# Schaltplan.net
KiCad netlist of a schematic drawn in EAGLE
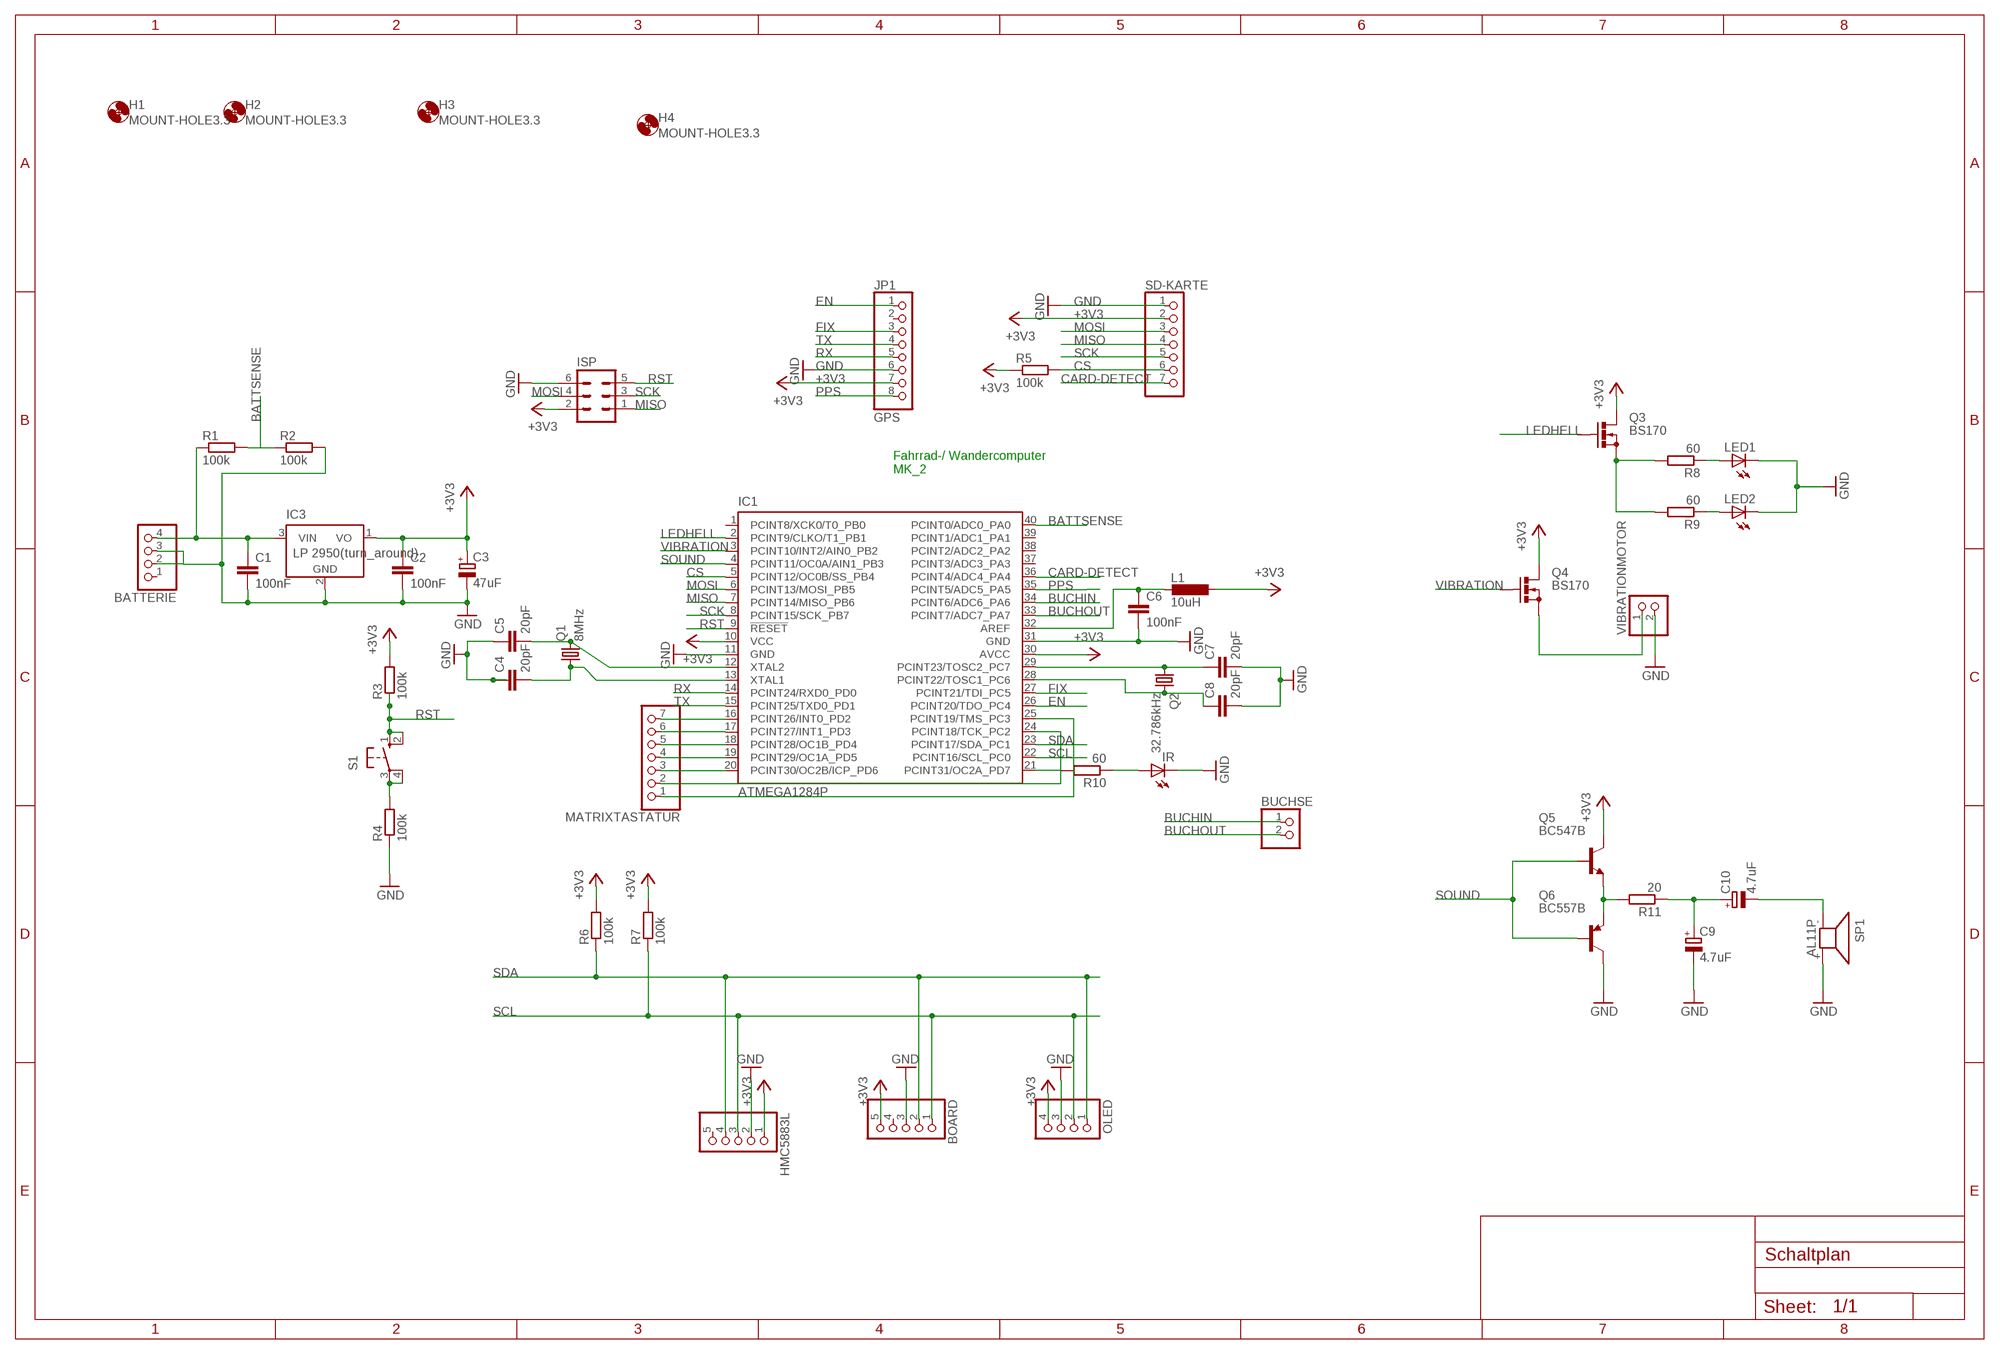
[diagram p0: schematic, sheet 1]

(export (version "E")
  (design (tool "Eeschema 10.0.6"))
  (components
    (comp (ref "BATTERIE")
      (value "PINHD-1X4")
      (footprint "eagle-import:1X04")
      (libsource (lib "eagle-import") (part "PINHD-1X4"))
    )
    (comp (ref "BOARD")
      (value "PINHD-1X5")
      (footprint "eagle-import:1X05")
      (libsource (lib "eagle-import") (part "PINHD-1X5"))
    )
    (comp (ref "BUCHSE")
      (value "PINHD-1X2")
      (footprint "eagle-import:1X02")
      (libsource (lib "eagle-import") (part "PINHD-1X2"))
    )
    (comp (ref "C1")
      (value "100nF")
      (footprint "eagle-import:C025-024X044")
      (libsource (lib "eagle-import") (part "C-EU025-024X044"))
    )
    (comp (ref "C2")
      (value "100nF")
      (footprint "eagle-import:C025-024X044")
      (libsource (lib "eagle-import") (part "C-EU025-024X044"))
    )
    (comp (ref "C3")
      (value "47uF")
      (footprint "eagle-import:E2,5-6")
      (libsource (lib "eagle-import") (part "CPOL-EUE2.5-6"))
    )
    (comp (ref "C4")
      (value "20pF")
      (footprint "eagle-import:C025-024X044")
      (libsource (lib "eagle-import") (part "C-EU025-024X044"))
    )
    (comp (ref "C5")
      (value "20pF")
      (footprint "eagle-import:C025-024X044")
      (libsource (lib "eagle-import") (part "C-EU025-024X044"))
    )
    (comp (ref "C6")
      (value "100nF")
      (footprint "eagle-import:C025-024X044")
      (libsource (lib "eagle-import") (part "C-EU025-024X044"))
    )
    (comp (ref "C7")
      (value "20pF")
      (footprint "eagle-import:C025-024X044")
      (libsource (lib "eagle-import") (part "C-EU025-024X044"))
    )
    (comp (ref "C8")
      (value "20pF")
      (footprint "eagle-import:C025-024X044")
      (libsource (lib "eagle-import") (part "C-EU025-024X044"))
    )
    (comp (ref "C9")
      (value "4.7uF")
      (footprint "eagle-import:E2,5-6")
      (libsource (lib "eagle-import") (part "CPOL-EUE2.5-6"))
    )
    (comp (ref "C10")
      (value "4.7uF")
      (footprint "eagle-import:E2,5-6")
      (libsource (lib "eagle-import") (part "CPOL-EUE2.5-6"))
    )
    (comp (ref "H1")
      (value "MOUNT-HOLE3.3")
      (footprint "eagle-import:3,3")
      (libsource (lib "eagle-import") (part "MOUNT-HOLE3.3"))
    )
    (comp (ref "H2")
      (value "MOUNT-HOLE3.3")
      (footprint "eagle-import:3,3")
      (libsource (lib "eagle-import") (part "MOUNT-HOLE3.3"))
    )
    (comp (ref "H3")
      (value "MOUNT-HOLE3.3")
      (footprint "eagle-import:3,3")
      (libsource (lib "eagle-import") (part "MOUNT-HOLE3.3"))
    )
    (comp (ref "H4")
      (value "MOUNT-HOLE3.3")
      (footprint "eagle-import:3,3")
      (libsource (lib "eagle-import") (part "MOUNT-HOLE3.3"))
    )
    (comp (ref "HMC5883L")
      (value "PINHD-1X5")
      (footprint "eagle-import:1X05")
      (libsource (lib "eagle-import") (part "PINHD-1X5"))
    )
    (comp (ref "IC1")
      (value "ATMEGA1284P")
      (footprint "eagle-import:DIL40")
      (fields (field (name "MPN") "ATMEGA644-20PU"))
      (libsource (lib "eagle-import") (part "ATMEGA644-PU20"))
    )
    (comp (ref "IC3")
      (value "LP 2950(turn_around)")
      (footprint "eagle-import:TO92")
      (fields (field (name "MF") "NATIONAL SEMICONDUCTOR") (field (name "MPN") "LM2936Z-3.0/NOPB"))
      (libsource (lib "eagle-import") (part "LM2936?Z-3.0"))
    )
    (comp (ref "IR")
      (value "LED3MM")
      (footprint "eagle-import:LED3MM")
      (libsource (lib "eagle-import") (part "LED3MM"))
    )
    (comp (ref "ISP")
      (value "ML6")
      (footprint "eagle-import:ML6")
      (libsource (lib "eagle-import") (part "ML6"))
    )
    (comp (ref "JP1")
      (value "GPS")
      (footprint "eagle-import:1X08")
      (libsource (lib "eagle-import") (part "PINHD-1X8"))
    )
    (comp (ref "L1")
      (value "10uH")
      (footprint "eagle-import:0207_10")
      (libsource (lib "eagle-import") (part "L-EU0207/10"))
    )
    (comp (ref "LED1")
      (value "LED5MM")
      (footprint "eagle-import:LED5MM")
      (libsource (lib "eagle-import") (part "LED5MM"))
    )
    (comp (ref "LED2")
      (value "LED5MM")
      (footprint "eagle-import:LED5MM")
      (libsource (lib "eagle-import") (part "LED5MM"))
    )
    (comp (ref "MATRIXTASTATUR")
      (value "PINHD-1X7")
      (footprint "eagle-import:1X07")
      (libsource (lib "eagle-import") (part "PINHD-1X7"))
    )
    (comp (ref "OLED")
      (value "PINHD-1X4")
      (footprint "eagle-import:1X04")
      (libsource (lib "eagle-import") (part "PINHD-1X4"))
    )
    (comp (ref "Q1")
      (value "8MHz")
      (footprint "eagle-import:HC49_S")
      (libsource (lib "eagle-import") (part "CRYSTALHC49S"))
    )
    (comp (ref "Q2")
      (value "32.786kHz")
      (footprint "eagle-import:TC26V")
      (libsource (lib "eagle-import") (part "CRYSTALTC26V"))
    )
    (comp (ref "Q3")
      (value "BS170")
      (footprint "eagle-import:SOT54E")
      (libsource (lib "eagle-import") (part "BS170"))
    )
    (comp (ref "Q4")
      (value "BS170")
      (footprint "eagle-import:SOT54E")
      (libsource (lib "eagle-import") (part "BS170"))
    )
    (comp (ref "Q5")
      (value "BC547B")
      (footprint "eagle-import:TO92")
      (libsource (lib "eagle-import") (part "BC547B"))
    )
    (comp (ref "Q6")
      (value "BC557B")
      (footprint "eagle-import:TO92-EBC")
      (libsource (lib "eagle-import") (part "BC557B"))
    )
    (comp (ref "R1")
      (value "100k")
      (footprint "eagle-import:0207_10")
      (libsource (lib "eagle-import") (part "R-EU_0207/10"))
    )
    (comp (ref "R2")
      (value "100k")
      (footprint "eagle-import:0207_10")
      (libsource (lib "eagle-import") (part "R-EU_0207/10"))
    )
    (comp (ref "R3")
      (value "100k")
      (footprint "eagle-import:0207_10")
      (libsource (lib "eagle-import") (part "R-EU_0207/10"))
    )
    (comp (ref "R4")
      (value "100k")
      (footprint "eagle-import:0207_10")
      (libsource (lib "eagle-import") (part "R-EU_0207/10"))
    )
    (comp (ref "R5")
      (value "100k")
      (footprint "eagle-import:0207_10")
      (libsource (lib "eagle-import") (part "R-EU_0207/10"))
    )
    (comp (ref "R6")
      (value "100k")
      (footprint "eagle-import:0207_10")
      (libsource (lib "eagle-import") (part "R-EU_0207/10"))
    )
    (comp (ref "R7")
      (value "100k")
      (footprint "eagle-import:0207_10")
      (libsource (lib "eagle-import") (part "R-EU_0207/10"))
    )
    (comp (ref "R8")
      (value "60")
      (footprint "eagle-import:0207_10")
      (libsource (lib "eagle-import") (part "R-EU_0207/10"))
    )
    (comp (ref "R9")
      (value "60")
      (footprint "eagle-import:0207_10")
      (libsource (lib "eagle-import") (part "R-EU_0207/10"))
    )
    (comp (ref "R10")
      (value "60")
      (footprint "eagle-import:0207_10")
      (libsource (lib "eagle-import") (part "R-EU_0207/10"))
    )
    (comp (ref "R11")
      (value "20")
      (footprint "eagle-import:0207_10")
      (libsource (lib "eagle-import") (part "R-EU_0207/10"))
    )
    (comp (ref "S1")
      (value "10-XX")
      (footprint "eagle-import:B3F-10XX")
      (fields (field (name "MPN") "B3F-1000"))
      (libsource (lib "eagle-import") (part "10-XX"))
    )
    (comp (ref "SD-KARTE")
      (value "PINHD-1X7")
      (footprint "eagle-import:1X07")
      (libsource (lib "eagle-import") (part "PINHD-1X7"))
    )
    (comp (ref "SP1")
      (value "AL11P")
      (footprint "eagle-import:AL11P")
      (libsource (lib "eagle-import") (part "AL11P"))
    )
    (comp (ref "VIBRATIONMOTOR")
      (value "PINHD-1X2")
      (footprint "eagle-import:1X02")
      (libsource (lib "eagle-import") (part "PINHD-1X2"))
    )
  )
  (nets
    (net (code "1") (name "+3V3") (class "Default")
      (node (ref "BOARD") (pin "5") (pinfunction "5_5") (pintype "passive"))
      (node (ref "C2") (pin "1") (pinfunction "1_1") (pintype "passive"))
      (node (ref "C3") (pin "+") (pinfunction "+_+") (pintype "passive"))
      (node (ref "HMC5883L") (pin "1") (pinfunction "1_1") (pintype "passive"))
      (node (ref "IC1") (pin "10") (pinfunction "VCC_10") (pintype "power_in"))
      (node (ref "IC1") (pin "30") (pinfunction "AVCC_30") (pintype "power_in"))
      (node (ref "IC3") (pin "1") (pinfunction "VO_1") (pintype "passive"))
      (node (ref "ISP") (pin "2") (pinfunction "2_2") (pintype "passive"))
      (node (ref "JP1") (pin "7") (pinfunction "7_7") (pintype "passive"))
      (node (ref "L1") (pin "1") (pinfunction "1_1") (pintype "passive"))
      (node (ref "OLED") (pin "4") (pinfunction "4_4") (pintype "passive"))
      (node (ref "Q3") (pin "D") (pinfunction "D_D") (pintype "passive"))
      (node (ref "Q4") (pin "D") (pinfunction "D_D") (pintype "passive"))
      (node (ref "Q5") (pin "3") (pinfunction "C_3") (pintype "passive"))
      (node (ref "R3") (pin "2") (pinfunction "2_2") (pintype "passive"))
      (node (ref "R5") (pin "1") (pinfunction "1_1") (pintype "passive"))
      (node (ref "R6") (pin "2") (pinfunction "2_2") (pintype "passive"))
      (node (ref "R7") (pin "2") (pinfunction "2_2") (pintype "passive"))
      (node (ref "SD-KARTE") (pin "2") (pinfunction "2_2") (pintype "passive"))
    )
    (net (code "2") (name "/BATTSENSE") (class "Default")
      (node (ref "IC1") (pin "40") (pinfunction "PCINT0/ADC0_PA0_40") (pintype "bidirectional"))
      (node (ref "R1") (pin "2") (pinfunction "2_2") (pintype "passive"))
      (node (ref "R2") (pin "1") (pinfunction "1_1") (pintype "passive"))
    )
    (net (code "3") (name "/BUCHIN") (class "Default")
      (node (ref "BUCHSE") (pin "1") (pinfunction "1_1") (pintype "passive"))
      (node (ref "IC1") (pin "34") (pinfunction "PCINT6/ADC6_PA6_34") (pintype "bidirectional"))
    )
    (net (code "4") (name "/BUCHOUT") (class "Default")
      (node (ref "BUCHSE") (pin "2") (pinfunction "2_2") (pintype "passive"))
      (node (ref "IC1") (pin "33") (pinfunction "PCINT7/ADC7_PA7_33") (pintype "bidirectional"))
    )
    (net (code "5") (name "/CARD-DETECT") (class "Default")
      (node (ref "IC1") (pin "36") (pinfunction "PCINT4/ADC4_PA4_36") (pintype "bidirectional"))
      (node (ref "SD-KARTE") (pin "7") (pinfunction "7_7") (pintype "passive"))
    )
    (net (code "6") (name "/CS") (class "Default")
      (node (ref "IC1") (pin "5") (pinfunction "PCINT12/OC0B/SS_PB4_5") (pintype "bidirectional"))
      (node (ref "R5") (pin "2") (pinfunction "2_2") (pintype "passive"))
      (node (ref "SD-KARTE") (pin "6") (pinfunction "6_6") (pintype "passive"))
    )
    (net (code "7") (name "/EN") (class "Default")
      (node (ref "IC1") (pin "26") (pinfunction "PCINT20/TDO_PC4_26") (pintype "bidirectional"))
      (node (ref "JP1") (pin "1") (pinfunction "1_1") (pintype "passive"))
    )
    (net (code "8") (name "/FIX") (class "Default")
      (node (ref "IC1") (pin "27") (pinfunction "PCINT21/TDI_PC5_27") (pintype "bidirectional"))
      (node (ref "JP1") (pin "3") (pinfunction "3_3") (pintype "passive"))
    )
    (net (code "9") (name "/LEDHELL") (class "Default")
      (node (ref "IC1") (pin "2") (pinfunction "PCINT9/CLKO/T1_PB1_2") (pintype "bidirectional"))
      (node (ref "Q3") (pin "G") (pinfunction "G_G") (pintype "passive"))
    )
    (net (code "10") (name "/MISO") (class "Default")
      (node (ref "IC1") (pin "7") (pinfunction "PCINT14/MISO_PB6_7") (pintype "bidirectional"))
      (node (ref "ISP") (pin "1") (pinfunction "1_1") (pintype "passive"))
      (node (ref "SD-KARTE") (pin "4") (pinfunction "4_4") (pintype "passive"))
    )
    (net (code "11") (name "/MOSI") (class "Default")
      (node (ref "IC1") (pin "6") (pinfunction "PCINT13/MOSI_PB5_6") (pintype "bidirectional"))
      (node (ref "ISP") (pin "4") (pinfunction "4_4") (pintype "passive"))
      (node (ref "SD-KARTE") (pin "3") (pinfunction "3_3") (pintype "passive"))
    )
    (net (code "12") (name "/PPS") (class "Default")
      (node (ref "IC1") (pin "35") (pinfunction "PCINT5/ADC5_PA5_35") (pintype "bidirectional"))
      (node (ref "JP1") (pin "8") (pinfunction "8_8") (pintype "passive"))
    )
    (net (code "13") (name "/RST") (class "Default")
      (node (ref "IC1") (pin "9") (pinfunction "~{RESET}_9") (pintype "input"))
      (node (ref "ISP") (pin "5") (pinfunction "5_5") (pintype "passive"))
      (node (ref "R3") (pin "1") (pinfunction "1_1") (pintype "passive"))
      (node (ref "S1") (pin "1") (pinfunction "S_1") (pintype "passive"))
      (node (ref "S1") (pin "2") (pinfunction "S1_2") (pintype "passive"))
    )
    (net (code "14") (name "/RX") (class "Default")
      (node (ref "IC1") (pin "14") (pinfunction "PCINT24/RXD0_PD0_14") (pintype "bidirectional"))
      (node (ref "JP1") (pin "5") (pinfunction "5_5") (pintype "passive"))
    )
    (net (code "15") (name "/SCK") (class "Default")
      (node (ref "IC1") (pin "8") (pinfunction "PCINT15/SCK_PB7_8") (pintype "bidirectional"))
      (node (ref "ISP") (pin "3") (pinfunction "3_3") (pintype "passive"))
      (node (ref "SD-KARTE") (pin "5") (pinfunction "5_5") (pintype "passive"))
    )
    (net (code "16") (name "/SCL") (class "Default")
      (node (ref "BOARD") (pin "1") (pinfunction "1_1") (pintype "passive"))
      (node (ref "HMC5883L") (pin "3") (pinfunction "3_3") (pintype "passive"))
      (node (ref "IC1") (pin "22") (pinfunction "PCINT16/SCL_PC0_22") (pintype "bidirectional"))
      (node (ref "OLED") (pin "2") (pinfunction "2_2") (pintype "passive"))
      (node (ref "R7") (pin "1") (pinfunction "1_1") (pintype "passive"))
    )
    (net (code "17") (name "/SDA") (class "Default")
      (node (ref "BOARD") (pin "2") (pinfunction "2_2") (pintype "passive"))
      (node (ref "HMC5883L") (pin "4") (pinfunction "4_4") (pintype "passive"))
      (node (ref "IC1") (pin "23") (pinfunction "PCINT17/SDA_PC1_23") (pintype "bidirectional"))
      (node (ref "OLED") (pin "1") (pinfunction "1_1") (pintype "passive"))
      (node (ref "R6") (pin "1") (pinfunction "1_1") (pintype "passive"))
    )
    (net (code "18") (name "/SOUND") (class "Default")
      (node (ref "IC1") (pin "4") (pinfunction "PCINT11/OC0A/AIN1_PB3_4") (pintype "bidirectional"))
      (node (ref "Q5") (pin "2") (pinfunction "B_2") (pintype "passive"))
      (node (ref "Q6") (pin "B") (pinfunction "B_B") (pintype "passive"))
    )
    (net (code "19") (name "/TX") (class "Default")
      (node (ref "IC1") (pin "15") (pinfunction "PCINT25/TXD0_PD1_15") (pintype "bidirectional"))
      (node (ref "JP1") (pin "4") (pinfunction "4_4") (pintype "passive"))
    )
    (net (code "20") (name "/VIBRATION") (class "Default")
      (node (ref "IC1") (pin "3") (pinfunction "PCINT10/INT2/AIN0_PB2_3") (pintype "bidirectional"))
      (node (ref "Q4") (pin "G") (pinfunction "G_G") (pintype "passive"))
    )
    (net (code "21") (name "GND") (class "Default")
      (node (ref "BATTERIE") (pin "2") (pinfunction "2_2") (pintype "passive"))
      (node (ref "BATTERIE") (pin "3") (pinfunction "3_3") (pintype "passive"))
      (node (ref "BOARD") (pin "3") (pinfunction "3_3") (pintype "passive"))
      (node (ref "C1") (pin "2") (pinfunction "2_2") (pintype "passive"))
      (node (ref "C2") (pin "2") (pinfunction "2_2") (pintype "passive"))
      (node (ref "C3") (pin "-") (pinfunction "-_-") (pintype "passive"))
      (node (ref "C4") (pin "1") (pinfunction "1_1") (pintype "passive"))
      (node (ref "C5") (pin "1") (pinfunction "1_1") (pintype "passive"))
      (node (ref "C6") (pin "2") (pinfunction "2_2") (pintype "passive"))
      (node (ref "C7") (pin "2") (pinfunction "2_2") (pintype "passive"))
      (node (ref "C8") (pin "2") (pinfunction "2_2") (pintype "passive"))
      (node (ref "C9") (pin "-") (pinfunction "-_-") (pintype "passive"))
      (node (ref "HMC5883L") (pin "2") (pinfunction "2_2") (pintype "passive"))
      (node (ref "IC1") (pin "11") (pinfunction "GND_11") (pintype "power_in"))
      (node (ref "IC1") (pin "31") (pinfunction "GND_31") (pintype "power_in"))
      (node (ref "IC3") (pin "2") (pinfunction "GND_2") (pintype "passive"))
      (node (ref "IR") (pin "K") (pinfunction "C_K") (pintype "passive"))
      (node (ref "ISP") (pin "6") (pinfunction "6_6") (pintype "passive"))
      (node (ref "JP1") (pin "6") (pinfunction "6_6") (pintype "passive"))
      (node (ref "LED1") (pin "K") (pinfunction "C_K") (pintype "passive"))
      (node (ref "LED2") (pin "K") (pinfunction "C_K") (pintype "passive"))
      (node (ref "OLED") (pin "3") (pinfunction "3_3") (pintype "passive"))
      (node (ref "Q6") (pin "C") (pinfunction "C_C") (pintype "passive"))
      (node (ref "R2") (pin "2") (pinfunction "2_2") (pintype "passive"))
      (node (ref "R4") (pin "1") (pinfunction "1_1") (pintype "passive"))
      (node (ref "SD-KARTE") (pin "1") (pinfunction "1_1") (pintype "passive"))
      (node (ref "SP1") (pin "+") (pinfunction "2_+") (pintype "passive"))
      (node (ref "VIBRATIONMOTOR") (pin "2") (pinfunction "2_2") (pintype "passive"))
    )
    (net (code "22") (name "Net-(C10-Pad+)") (class "Default")
      (node (ref "C10") (pin "+") (pinfunction "+_+") (pintype "passive"))
      (node (ref "C9") (pin "+") (pinfunction "+_+") (pintype "passive"))
      (node (ref "R11") (pin "1") (pinfunction "1_1") (pintype "passive"))
    )
    (net (code "23") (name "Net-(IC1-AREF)") (class "Default")
      (node (ref "C6") (pin "1") (pinfunction "1_1") (pintype "passive"))
      (node (ref "IC1") (pin "32") (pinfunction "AREF_32") (pintype "passive"))
      (node (ref "L1") (pin "2") (pinfunction "2_2") (pintype "passive"))
    )
    (net (code "24") (name "Net-(IC1-PCINT18{slash}TCK_PC2)") (class "Default")
      (node (ref "IC1") (pin "24") (pinfunction "PCINT18/TCK_PC2_24") (pintype "bidirectional"))
      (node (ref "MATRIXTASTATUR") (pin "2") (pinfunction "2_2") (pintype "passive"))
    )
    (net (code "25") (name "Net-(IC1-PCINT19{slash}TMS_PC3)") (class "Default")
      (node (ref "IC1") (pin "25") (pinfunction "PCINT19/TMS_PC3_25") (pintype "bidirectional"))
      (node (ref "MATRIXTASTATUR") (pin "1") (pinfunction "1_1") (pintype "passive"))
    )
    (net (code "26") (name "Net-(IC1-PCINT22{slash}TOSC1_PC6)") (class "Default")
      (node (ref "C8") (pin "1") (pinfunction "1_1") (pintype "passive"))
      (node (ref "IC1") (pin "28") (pinfunction "PCINT22/TOSC1_PC6_28") (pintype "bidirectional"))
      (node (ref "Q2") (pin "2") (pinfunction "2_2") (pintype "passive"))
    )
    (net (code "27") (name "Net-(IC1-PCINT23{slash}TOSC2_PC7)") (class "Default")
      (node (ref "C7") (pin "1") (pinfunction "1_1") (pintype "passive"))
      (node (ref "IC1") (pin "29") (pinfunction "PCINT23/TOSC2_PC7_29") (pintype "bidirectional"))
      (node (ref "Q2") (pin "1") (pinfunction "1_1") (pintype "passive"))
    )
    (net (code "28") (name "Net-(IC1-PCINT26{slash}INT0_PD2)") (class "Default")
      (node (ref "IC1") (pin "16") (pinfunction "PCINT26/INT0_PD2_16") (pintype "bidirectional"))
      (node (ref "MATRIXTASTATUR") (pin "7") (pinfunction "7_7") (pintype "passive"))
    )
    (net (code "29") (name "Net-(IC1-PCINT27{slash}INT1_PD3)") (class "Default")
      (node (ref "IC1") (pin "17") (pinfunction "PCINT27/INT1_PD3_17") (pintype "bidirectional"))
      (node (ref "MATRIXTASTATUR") (pin "6") (pinfunction "6_6") (pintype "passive"))
    )
    (net (code "30") (name "Net-(IC1-PCINT28{slash}OC1B_PD4)") (class "Default")
      (node (ref "IC1") (pin "18") (pinfunction "PCINT28/OC1B_PD4_18") (pintype "bidirectional"))
      (node (ref "MATRIXTASTATUR") (pin "5") (pinfunction "5_5") (pintype "passive"))
    )
    (net (code "31") (name "Net-(IC1-PCINT29{slash}OC1A_PD5)") (class "Default")
      (node (ref "IC1") (pin "19") (pinfunction "PCINT29/OC1A_PD5_19") (pintype "bidirectional"))
      (node (ref "MATRIXTASTATUR") (pin "4") (pinfunction "4_4") (pintype "passive"))
    )
    (net (code "32") (name "Net-(IC1-PCINT30{slash}OC2B{slash}ICP_PD6)") (class "Default")
      (node (ref "IC1") (pin "20") (pinfunction "PCINT30/OC2B/ICP_PD6_20") (pintype "bidirectional"))
      (node (ref "MATRIXTASTATUR") (pin "3") (pinfunction "3_3") (pintype "passive"))
    )
    (net (code "33") (name "Net-(IC1-PCINT31{slash}OC2A_PD7)") (class "Default")
      (node (ref "IC1") (pin "21") (pinfunction "PCINT31/OC2A_PD7_21") (pintype "bidirectional"))
      (node (ref "R10") (pin "2") (pinfunction "2_2") (pintype "passive"))
    )
    (net (code "34") (name "Net-(IC1-XTAL1)") (class "Default")
      (node (ref "C4") (pin "2") (pinfunction "2_2") (pintype "passive"))
      (node (ref "IC1") (pin "13") (pinfunction "XTAL1_13") (pintype "input"))
      (node (ref "Q1") (pin "1") (pinfunction "1_1") (pintype "passive"))
    )
    (net (code "35") (name "Net-(IC1-XTAL2)") (class "Default")
      (node (ref "C5") (pin "2") (pinfunction "2_2") (pintype "passive"))
      (node (ref "IC1") (pin "12") (pinfunction "XTAL2_12") (pintype "output"))
      (node (ref "Q1") (pin "2") (pinfunction "2_2") (pintype "passive"))
    )
    (net (code "36") (name "Net-(IC3-VIN)") (class "Default")
      (node (ref "BATTERIE") (pin "4") (pinfunction "4_4") (pintype "passive"))
      (node (ref "C1") (pin "1") (pinfunction "1_1") (pintype "passive"))
      (node (ref "IC3") (pin "3") (pinfunction "VIN_3") (pintype "input"))
      (node (ref "R1") (pin "1") (pinfunction "1_1") (pintype "passive"))
    )
    (net (code "37") (name "Net-(IR-PadA)") (class "Default")
      (node (ref "IR") (pin "A") (pinfunction "A_A") (pintype "passive"))
      (node (ref "R10") (pin "1") (pinfunction "1_1") (pintype "passive"))
    )
    (net (code "38") (name "Net-(LED1-PadA)") (class "Default")
      (node (ref "LED1") (pin "A") (pinfunction "A_A") (pintype "passive"))
      (node (ref "R8") (pin "1") (pinfunction "1_1") (pintype "passive"))
    )
    (net (code "39") (name "Net-(LED2-PadA)") (class "Default")
      (node (ref "LED2") (pin "A") (pinfunction "A_A") (pintype "passive"))
      (node (ref "R9") (pin "1") (pinfunction "1_1") (pintype "passive"))
    )
    (net (code "40") (name "Net-(Q3-PadS)") (class "Default")
      (node (ref "Q3") (pin "S") (pinfunction "S_S") (pintype "passive"))
      (node (ref "R8") (pin "2") (pinfunction "2_2") (pintype "passive"))
      (node (ref "R9") (pin "2") (pinfunction "2_2") (pintype "passive"))
    )
    (net (code "41") (name "Net-(Q4-PadS)") (class "Default")
      (node (ref "Q4") (pin "S") (pinfunction "S_S") (pintype "passive"))
      (node (ref "VIBRATIONMOTOR") (pin "1") (pinfunction "1_1") (pintype "passive"))
    )
    (net (code "42") (name "Net-(Q5-E)") (class "Default")
      (node (ref "Q5") (pin "1") (pinfunction "E_1") (pintype "passive"))
      (node (ref "Q6") (pin "E") (pinfunction "E_E") (pintype "passive"))
      (node (ref "R11") (pin "2") (pinfunction "2_2") (pintype "passive"))
    )
    (net (code "43") (name "Net-(S1-P)") (class "Default")
      (node (ref "R4") (pin "2") (pinfunction "2_2") (pintype "passive"))
      (node (ref "S1") (pin "3") (pinfunction "P_3") (pintype "passive"))
      (node (ref "S1") (pin "4") (pinfunction "P1_4") (pintype "passive"))
    )
    (net (code "44") (name "Net-(SP1-1)") (class "Default")
      (node (ref "C10") (pin "-") (pinfunction "-_-") (pintype "passive"))
      (node (ref "SP1") (pin "-") (pinfunction "1_-") (pintype "passive"))
    )
    (net (code "45") (name "unconnected-(BATTERIE-Pad1)") (class "Default")
      (node (ref "BATTERIE") (pin "1") (pinfunction "1_1") (pintype "passive"))
    )
    (net (code "46") (name "unconnected-(BOARD-Pad4)") (class "Default")
      (node (ref "BOARD") (pin "4") (pinfunction "4_4") (pintype "passive"))
    )
    (net (code "47") (name "unconnected-(HMC5883L-Pad5)") (class "Default")
      (node (ref "HMC5883L") (pin "5") (pinfunction "5_5") (pintype "passive"))
    )
    (net (code "48") (name "unconnected-(IC1-PCINT1{slash}ADC1_PA1-Pad39)") (class "Default")
      (node (ref "IC1") (pin "39") (pinfunction "PCINT1/ADC1_PA1_39") (pintype "bidirectional"))
    )
    (net (code "49") (name "unconnected-(IC1-PCINT2{slash}ADC2_PA2-Pad38)") (class "Default")
      (node (ref "IC1") (pin "38") (pinfunction "PCINT2/ADC2_PA2_38") (pintype "bidirectional"))
    )
    (net (code "50") (name "unconnected-(IC1-PCINT3{slash}ADC3_PA3-Pad37)") (class "Default")
      (node (ref "IC1") (pin "37") (pinfunction "PCINT3/ADC3_PA3_37") (pintype "bidirectional"))
    )
    (net (code "51") (name "unconnected-(IC1-PCINT8{slash}XCK0{slash}T0_PB0-Pad1)") (class "Default")
      (node (ref "IC1") (pin "1") (pinfunction "PCINT8/XCK0/T0_PB0_1") (pintype "bidirectional"))
    )
    (net (code "52") (name "unconnected-(JP1-Pad2)") (class "Default")
      (node (ref "JP1") (pin "2") (pinfunction "2_2") (pintype "passive"))
    )
  )
)
